# Stackduino-SMD.net
KiCad netlist of a schematic drawn in EAGLE
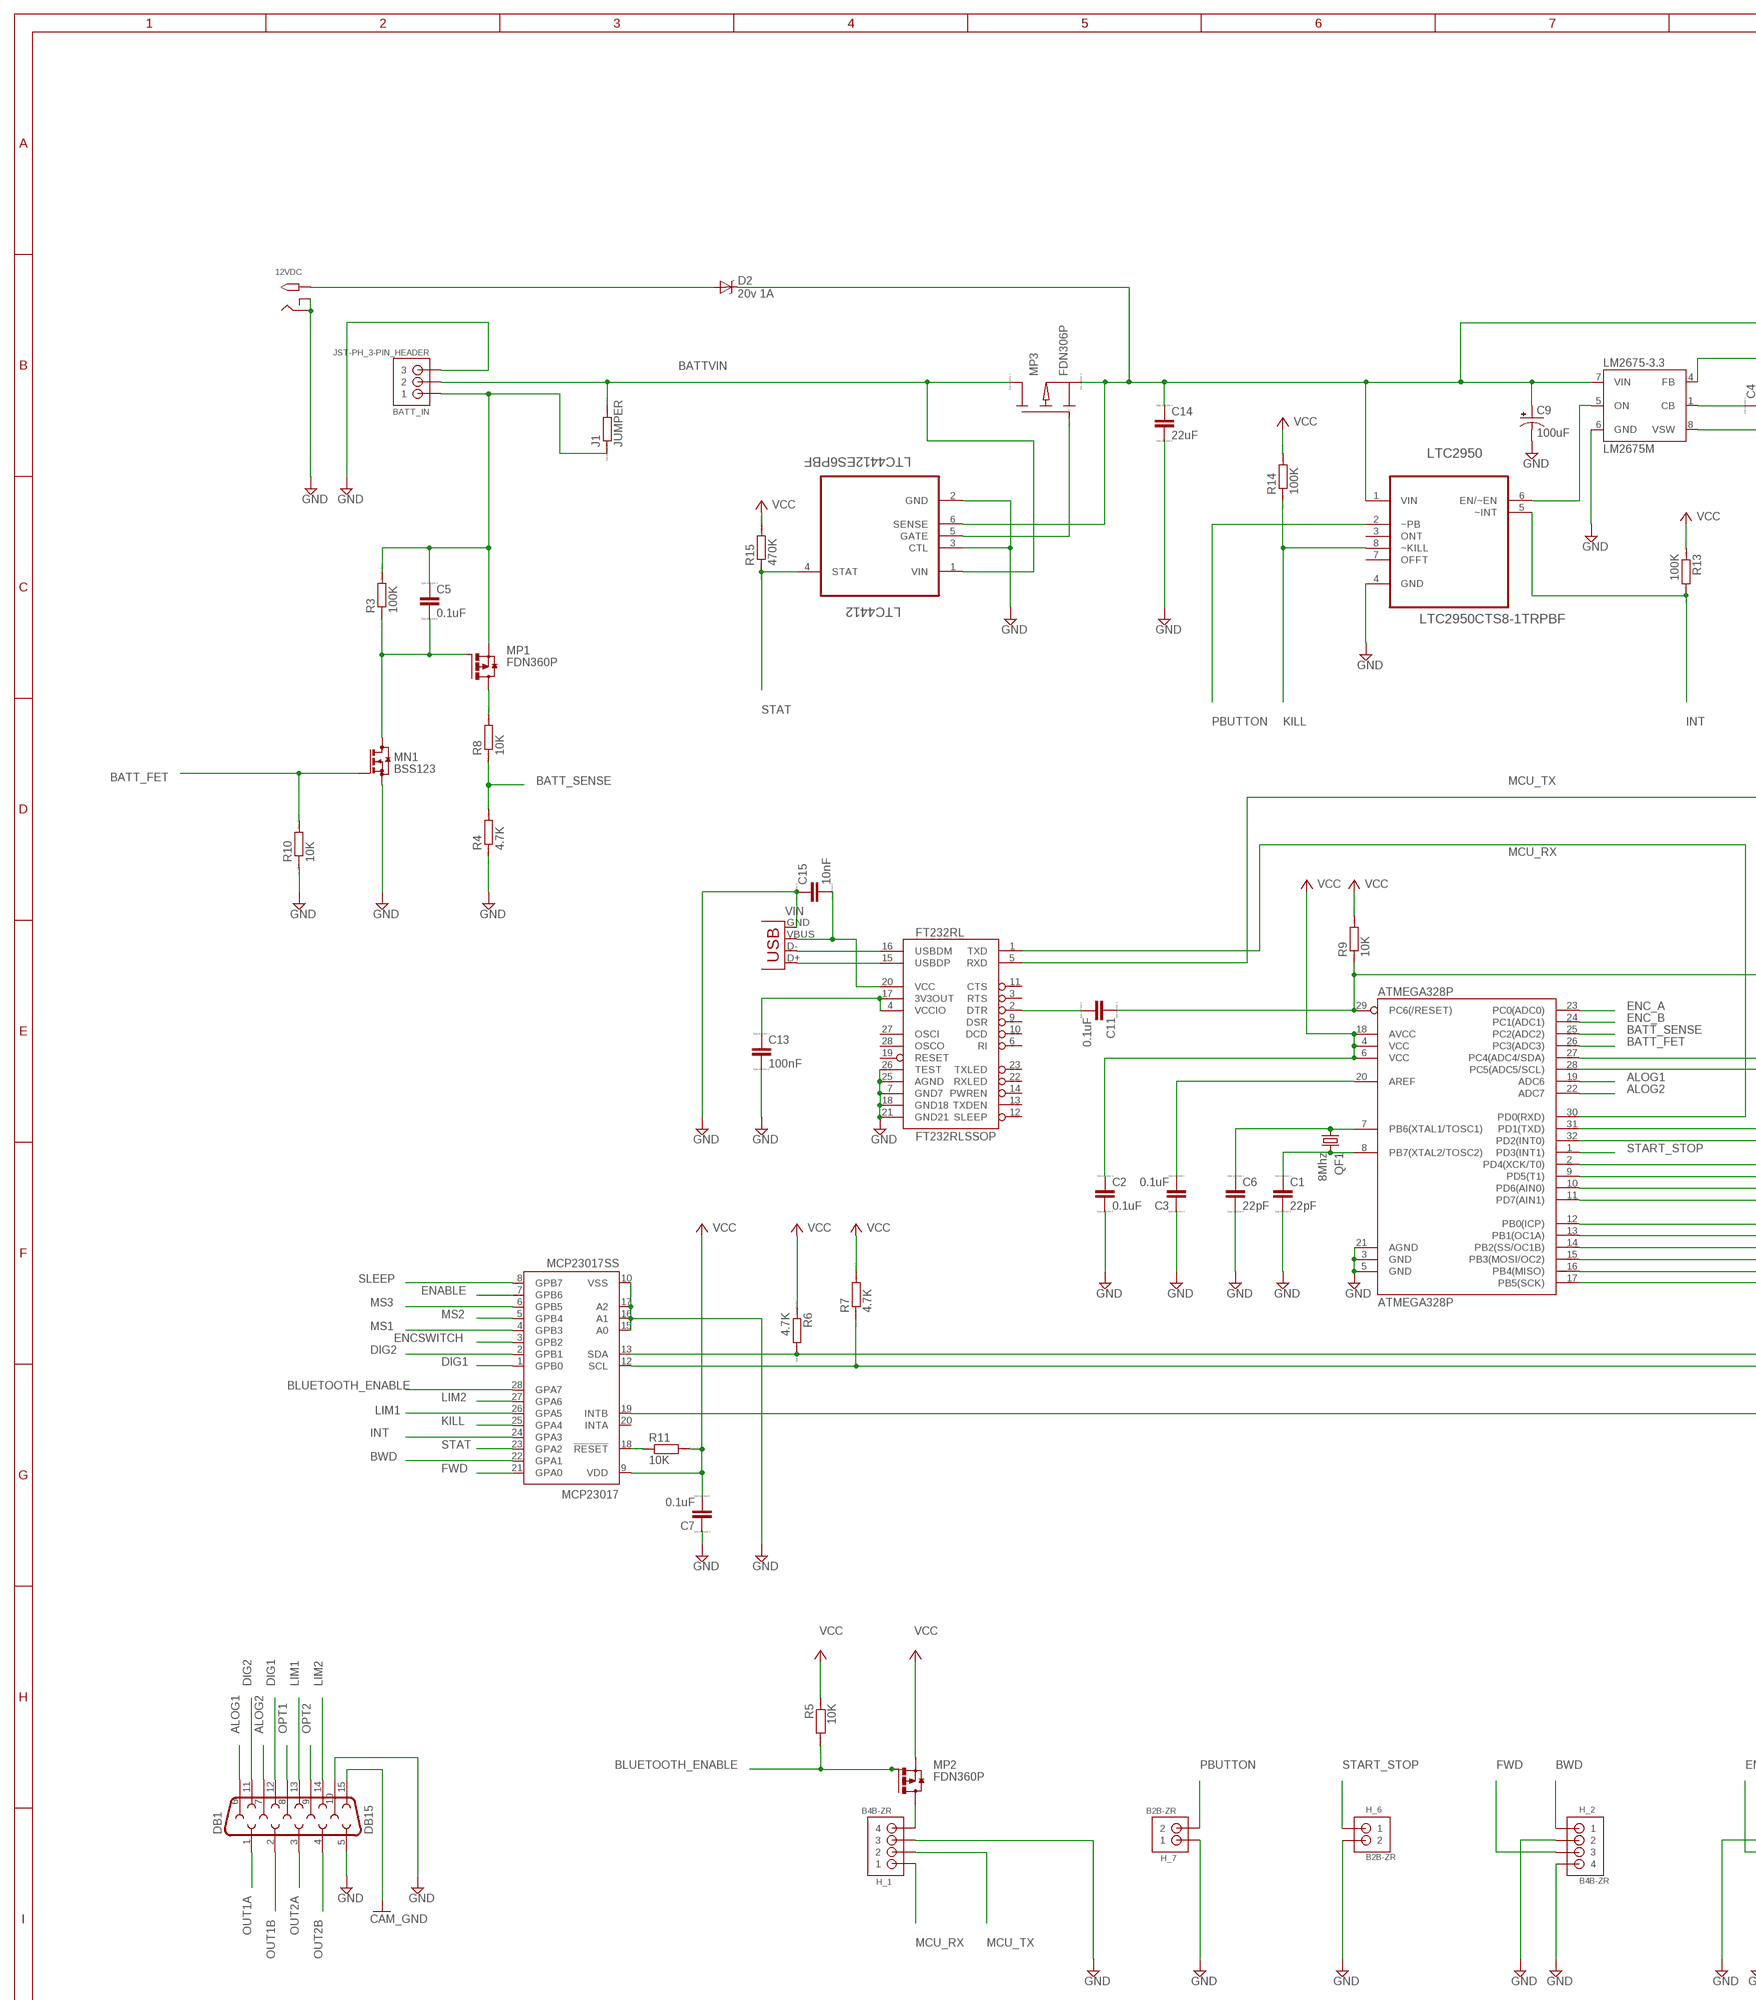
[diagram p0: schematic, sheet 1, part 1 of 2]
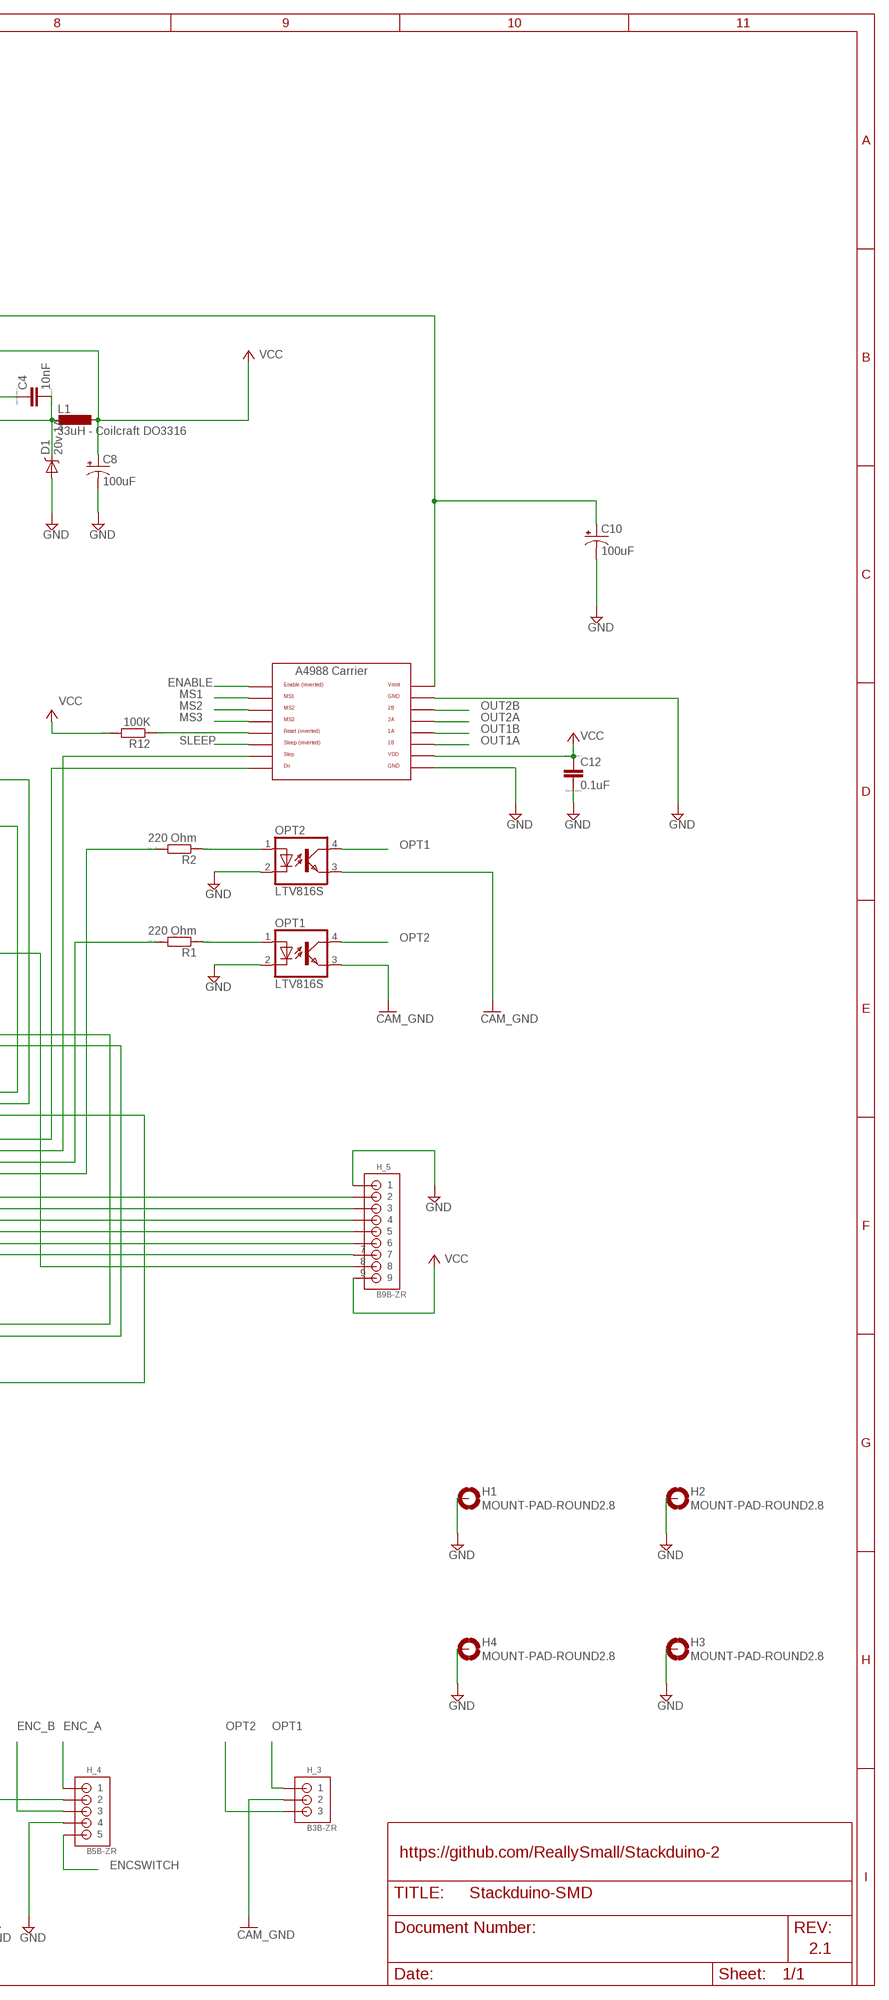
[diagram p1: schematic, sheet 1, part 2 of 2]

(export (version "E")
  (design (tool "Eeschema 10.0.6"))
  (components
    (comp (ref "12VDC")
      (value "2.1MMJACKTHM")
      (footprint "eagle-import:PJ-102A")
      (libsource (lib "eagle-import") (part "2.1MMJACKTHM"))
    )
    (comp (ref "A4988_CARRIER")
      (value "A4988BREAKOUT")
      (footprint "eagle-import:A4988BREAKOUT")
      (libsource (lib "eagle-import") (part "A4988BREAKOUT"))
    )
    (comp (ref "ATMEGA328P")
      (value "ATMEGA328P")
      (footprint "eagle-import:TQFP32-08")
      (libsource (lib "eagle-import") (part "ATMEGA328_SMT"))
    )
    (comp (ref "BATT_IN")
      (value "JST-PH_3-PIN_HEADER")
      (footprint "eagle-import:JST_B3B-PH_HEADER")
      (libsource (lib "eagle-import") (part "JST-PH_3-PIN_HEADER"))
    )
    (comp (ref "C1")
      (value "22pF")
      (footprint "eagle-import:C0805")
      (libsource (lib "eagle-import") (part "C"))
    )
    (comp (ref "C2")
      (value "0.1uF")
      (footprint "eagle-import:C0805")
      (libsource (lib "eagle-import") (part "C"))
    )
    (comp (ref "C3")
      (value "0.1uF")
      (footprint "eagle-import:C0805")
      (libsource (lib "eagle-import") (part "C"))
    )
    (comp (ref "C4")
      (value "10nF")
      (footprint "eagle-import:C0805")
      (libsource (lib "eagle-import") (part "C"))
    )
    (comp (ref "C5")
      (value "0.1uF")
      (footprint "eagle-import:C0805")
      (libsource (lib "eagle-import") (part "C"))
    )
    (comp (ref "C6")
      (value "22pF")
      (footprint "eagle-import:C0805")
      (libsource (lib "eagle-import") (part "C"))
    )
    (comp (ref "C7")
      (value "0.1uF")
      (footprint "eagle-import:C0805")
      (libsource (lib "eagle-import") (part "C"))
    )
    (comp (ref "C8")
      (value "100uF")
      (footprint "eagle-import:PANASONIC_D")
      (libsource (lib "eagle-import") (part "CAP_POLD"))
    )
    (comp (ref "C9")
      (value "100uF")
      (footprint "eagle-import:PANASONIC_D")
      (libsource (lib "eagle-import") (part "CAP_POLD"))
    )
    (comp (ref "C10")
      (value "100uF")
      (footprint "eagle-import:PANASONIC_D")
      (libsource (lib "eagle-import") (part "CAP_POLD"))
    )
    (comp (ref "C11")
      (value "0.1uF")
      (footprint "eagle-import:C0805")
      (libsource (lib "eagle-import") (part "C"))
    )
    (comp (ref "C12")
      (value "0.1uF")
      (footprint "eagle-import:C0805")
      (libsource (lib "eagle-import") (part "C"))
    )
    (comp (ref "C13")
      (value "100nF")
      (footprint "eagle-import:C0805")
      (libsource (lib "eagle-import") (part "C"))
    )
    (comp (ref "C14")
      (value "22uF")
      (footprint "eagle-import:C0805")
      (libsource (lib "eagle-import") (part "C"))
    )
    (comp (ref "C15")
      (value "10nF")
      (footprint "eagle-import:C0805")
      (libsource (lib "eagle-import") (part "C"))
    )
    (comp (ref "D1")
      (value "20v 1A")
      (footprint "eagle-import:SMA-DIODE")
      (libsource (lib "eagle-import") (part "MBRA140"))
    )
    (comp (ref "D2")
      (value "20v 1A")
      (footprint "eagle-import:SMA-DIODE")
      (libsource (lib "eagle-import") (part "MBRA140"))
    )
    (comp (ref "DB1")
      (value "DB15")
      (footprint "eagle-import:DB15")
      (libsource (lib "eagle-import") (part "DB15"))
    )
    (comp (ref "FT232RL")
      (value "FT232RLSSOP")
      (footprint "eagle-import:SSOP28DB")
      (libsource (lib "eagle-import") (part "FT232RLSSOP"))
    )
    (comp (ref "H1")
      (value "MOUNT-PAD-ROUND2.8")
      (footprint "eagle-import:2,8-PAD")
      (libsource (lib "eagle-import") (part "MOUNT-PAD-ROUND2.8"))
    )
    (comp (ref "H2")
      (value "MOUNT-PAD-ROUND2.8")
      (footprint "eagle-import:2,8-PAD")
      (libsource (lib "eagle-import") (part "MOUNT-PAD-ROUND2.8"))
    )
    (comp (ref "H3")
      (value "MOUNT-PAD-ROUND2.8")
      (footprint "eagle-import:2,8-PAD")
      (libsource (lib "eagle-import") (part "MOUNT-PAD-ROUND2.8"))
    )
    (comp (ref "H4")
      (value "MOUNT-PAD-ROUND2.8")
      (footprint "eagle-import:2,8-PAD")
      (libsource (lib "eagle-import") (part "MOUNT-PAD-ROUND2.8"))
    )
    (comp (ref "H_1")
      (value "B4B-ZR")
      (footprint "eagle-import:B4B-ZR")
      (libsource (lib "eagle-import") (part "B4B-ZR"))
    )
    (comp (ref "H_2")
      (value "B4B-ZR")
      (footprint "eagle-import:B4B-ZR")
      (libsource (lib "eagle-import") (part "B4B-ZR"))
    )
    (comp (ref "H_3")
      (value "B3B-ZR")
      (footprint "eagle-import:B3B-ZR")
      (libsource (lib "eagle-import") (part "B3B-ZR"))
    )
    (comp (ref "H_4")
      (value "B5B-ZR")
      (footprint "eagle-import:B5B-ZR")
      (libsource (lib "eagle-import") (part "B5B-ZR"))
    )
    (comp (ref "H_5")
      (value "B9B-ZR")
      (footprint "eagle-import:B9B-ZR")
      (libsource (lib "eagle-import") (part "B9B-ZR"))
    )
    (comp (ref "H_6")
      (value "B2B-ZR")
      (footprint "eagle-import:B2B-ZR")
      (libsource (lib "eagle-import") (part "B2B-ZR"))
    )
    (comp (ref "H_7")
      (value "B2B-ZR")
      (footprint "eagle-import:B2B-ZR")
      (libsource (lib "eagle-import") (part "B2B-ZR"))
    )
    (comp (ref "J1")
      (value "JUMPER")
      (footprint "eagle-import:R0805")
      (libsource (lib "eagle-import") (part "R"))
    )
    (comp (ref "L1")
      (value "33uH - Coilcraft DO3316")
      (footprint "eagle-import:DO3316P")
      (libsource (lib "eagle-import") (part "DO3316P"))
    )
    (comp (ref "LM2675-3.3")
      (value "LM2675M")
      (footprint "eagle-import:SO08")
      (libsource (lib "eagle-import") (part "LM2675M"))
    )
    (comp (ref "LTC2950")
      (value "LTC2950CTS8-1TRPBF")
      (footprint "eagle-import:SOT65P280X100-8N")
      (fields (field (name "MPN") "LTC2950CTS8-1#TRPBF"))
      (libsource (lib "eagle-import") (part "LTC2950CTS8-1TRPBF"))
    )
    (comp (ref "LTC4412")
      (value "LTC4412ES6PBF")
      (footprint "eagle-import:SOT95P280X100-6N")
      (fields (field (name "MPN") "LTC4412ES6#PBF"))
      (libsource (lib "eagle-import") (part "LTC4412ES6PBF"))
    )
    (comp (ref "MCP23017")
      (value "MCP23017SS")
      (footprint "eagle-import:SSOP28")
      (libsource (lib "eagle-import") (part "MCP23017SS"))
    )
    (comp (ref "MN1")
      (value "BSS123")
      (footprint "eagle-import:SOT23")
      (libsource (lib "eagle-import") (part "BSS123"))
    )
    (comp (ref "MP1")
      (value "FDN360P")
      (footprint "eagle-import:SUPER-SOT3")
      (libsource (lib "eagle-import") (part "FDN360P"))
    )
    (comp (ref "MP2")
      (value "FDN360P")
      (footprint "eagle-import:SUPER-SOT3")
      (libsource (lib "eagle-import") (part "FDN360P"))
    )
    (comp (ref "MP3")
      (value "FDN306P")
      (footprint "eagle-import:SOT23")
      (libsource (lib "eagle-import") (part "PMOS"))
    )
    (comp (ref "OPT1")
      (value "LTV816S")
      (footprint "eagle-import:SMD4")
      (libsource (lib "eagle-import") (part "LTV816S"))
    )
    (comp (ref "OPT2")
      (value "LTV816S")
      (footprint "eagle-import:SMD4")
      (libsource (lib "eagle-import") (part "LTV816S"))
    )
    (comp (ref "QF1")
      (value "8Mhz")
      (footprint "eagle-import:HC49U-V")
      (libsource (lib "eagle-import") (part "CRYSTALHC49U-V"))
    )
    (comp (ref "R1")
      (value "220 Ohm")
      (footprint "eagle-import:R0805")
      (libsource (lib "eagle-import") (part "R"))
    )
    (comp (ref "R2")
      (value "220 Ohm")
      (footprint "eagle-import:R0805")
      (libsource (lib "eagle-import") (part "R"))
    )
    (comp (ref "R3")
      (value "100K")
      (footprint "eagle-import:R0805")
      (libsource (lib "eagle-import") (part "R"))
    )
    (comp (ref "R4")
      (value "4.7K")
      (footprint "eagle-import:R0805")
      (libsource (lib "eagle-import") (part "R"))
    )
    (comp (ref "R5")
      (value "10K")
      (footprint "eagle-import:R0805")
      (libsource (lib "eagle-import") (part "R"))
    )
    (comp (ref "R6")
      (value "4.7K")
      (footprint "eagle-import:R0805")
      (libsource (lib "eagle-import") (part "R"))
    )
    (comp (ref "R7")
      (value "4.7K")
      (footprint "eagle-import:R0805")
      (libsource (lib "eagle-import") (part "R"))
    )
    (comp (ref "R8")
      (value "10K")
      (footprint "eagle-import:R0805")
      (libsource (lib "eagle-import") (part "R"))
    )
    (comp (ref "R9")
      (value "10K")
      (footprint "eagle-import:R0805")
      (libsource (lib "eagle-import") (part "R"))
    )
    (comp (ref "R10")
      (value "10K")
      (footprint "eagle-import:R0805")
      (libsource (lib "eagle-import") (part "R"))
    )
    (comp (ref "R11")
      (value "10K")
      (footprint "eagle-import:R0805")
      (libsource (lib "eagle-import") (part "R"))
    )
    (comp (ref "R12")
      (value "100K")
      (footprint "eagle-import:R0805")
      (libsource (lib "eagle-import") (part "R"))
    )
    (comp (ref "R13")
      (value "100K")
      (footprint "eagle-import:R0805")
      (libsource (lib "eagle-import") (part "R"))
    )
    (comp (ref "R14")
      (value "100K")
      (footprint "eagle-import:R0805")
      (libsource (lib "eagle-import") (part "R"))
    )
    (comp (ref "R15")
      (value "470K")
      (footprint "eagle-import:R0805")
      (libsource (lib "eagle-import") (part "R"))
    )
    (comp (ref "USB")
      (value "USBSMD")
      (footprint "eagle-import:USB-MINIB")
      (libsource (lib "eagle-import") (part "USBSMD"))
    )
  )
  (nets
    (net (code "1") (name "/ALOG1") (class "Default")
      (node (ref "ATMEGA328P") (pin "19") (pinfunction "ADC6_19") (pintype "bidirectional"))
      (node (ref "DB1") (pin "6") (pinfunction "6_6") (pintype "passive"))
    )
    (net (code "2") (name "/ALOG2") (class "Default")
      (node (ref "ATMEGA328P") (pin "22") (pinfunction "ADC7_22") (pintype "bidirectional"))
      (node (ref "DB1") (pin "7") (pinfunction "7_7") (pintype "passive"))
    )
    (net (code "3") (name "/BATTVIN") (class "Default")
      (node (ref "BATT_IN") (pin "P2") (pinfunction "2_P2") (pintype "bidirectional"))
      (node (ref "J1") (pin "2") (pinfunction "2_2") (pintype "passive"))
      (node (ref "LTC4412") (pin "1") (pinfunction "VIN_1") (pintype "power_in"))
      (node (ref "MP3") (pin "3") (pinfunction "D_3") (pintype "passive"))
    )
    (net (code "4") (name "/BATT_FET") (class "Default")
      (node (ref "ATMEGA328P") (pin "26") (pinfunction "PC3(ADC3)_26") (pintype "bidirectional"))
      (node (ref "MN1") (pin "1") (pinfunction "G_1") (pintype "passive"))
      (node (ref "R10") (pin "2") (pinfunction "2_2") (pintype "passive"))
    )
    (net (code "5") (name "/BATT_SENSE") (class "Default")
      (node (ref "ATMEGA328P") (pin "25") (pinfunction "PC2(ADC2)_25") (pintype "bidirectional"))
      (node (ref "R4") (pin "2") (pinfunction "2_2") (pintype "passive"))
      (node (ref "R8") (pin "1") (pinfunction "1_1") (pintype "passive"))
    )
    (net (code "6") (name "/BLUETOOTH_ENABLE") (class "Default")
      (node (ref "MCP23017") (pin "28") (pinfunction "GPA7_28") (pintype "bidirectional"))
      (node (ref "MP2") (pin "1") (pinfunction "G_1") (pintype "passive"))
      (node (ref "R5") (pin "2") (pinfunction "2_2") (pintype "passive"))
    )
    (net (code "7") (name "/BWD") (class "Default")
      (node (ref "H_2") (pin "1") (pinfunction "1_1") (pintype "bidirectional"))
      (node (ref "MCP23017") (pin "22") (pinfunction "GPA1_22") (pintype "bidirectional"))
    )
    (net (code "8") (name "/DIG1") (class "Default")
      (node (ref "DB1") (pin "12") (pinfunction "12_12") (pintype "passive"))
      (node (ref "MCP23017") (pin "1") (pinfunction "GPB0_1") (pintype "bidirectional"))
    )
    (net (code "9") (name "/DIG2") (class "Default")
      (node (ref "DB1") (pin "11") (pinfunction "11_11") (pintype "passive"))
      (node (ref "MCP23017") (pin "2") (pinfunction "GPB1_2") (pintype "bidirectional"))
    )
    (net (code "10") (name "/ENABLE") (class "Default")
      (node (ref "A4988_CARRIER") (pin "EN") (pinfunction "EN_EN") (pintype "input"))
      (node (ref "MCP23017") (pin "7") (pinfunction "GPB6_7") (pintype "bidirectional"))
    )
    (net (code "11") (name "/ENCSWITCH") (class "Default")
      (node (ref "H_4") (pin "5") (pinfunction "5_5") (pintype "bidirectional"))
      (node (ref "MCP23017") (pin "3") (pinfunction "GPB2_3") (pintype "bidirectional"))
    )
    (net (code "12") (name "/ENC_A") (class "Default")
      (node (ref "ATMEGA328P") (pin "23") (pinfunction "PC0(ADC0)_23") (pintype "bidirectional"))
      (node (ref "H_4") (pin "1") (pinfunction "1_1") (pintype "bidirectional"))
    )
    (net (code "13") (name "/ENC_B") (class "Default")
      (node (ref "ATMEGA328P") (pin "24") (pinfunction "PC1(ADC1)_24") (pintype "bidirectional"))
      (node (ref "H_4") (pin "3") (pinfunction "3_3") (pintype "bidirectional"))
    )
    (net (code "14") (name "/FWD") (class "Default")
      (node (ref "H_2") (pin "3") (pinfunction "3_3") (pintype "bidirectional"))
      (node (ref "MCP23017") (pin "21") (pinfunction "GPA0_21") (pintype "bidirectional"))
    )
    (net (code "15") (name "/INT") (class "Default")
      (node (ref "LTC2950") (pin "5") (pinfunction "~{INT}_5") (pintype "output"))
      (node (ref "MCP23017") (pin "24") (pinfunction "GPA3_24") (pintype "bidirectional"))
      (node (ref "R13") (pin "2") (pinfunction "2_2") (pintype "passive"))
    )
    (net (code "16") (name "/KILL") (class "Default")
      (node (ref "LTC2950") (pin "8") (pinfunction "~{KILL}_8") (pintype "input"))
      (node (ref "MCP23017") (pin "25") (pinfunction "GPA4_25") (pintype "bidirectional"))
      (node (ref "R14") (pin "1") (pinfunction "1_1") (pintype "passive"))
    )
    (net (code "17") (name "/LIM1") (class "Default")
      (node (ref "DB1") (pin "13") (pinfunction "13_13") (pintype "passive"))
      (node (ref "MCP23017") (pin "26") (pinfunction "GPA5_26") (pintype "bidirectional"))
    )
    (net (code "18") (name "/LIM2") (class "Default")
      (node (ref "DB1") (pin "14") (pinfunction "14_14") (pintype "passive"))
      (node (ref "MCP23017") (pin "27") (pinfunction "GPA6_27") (pintype "bidirectional"))
    )
    (net (code "19") (name "/MCU_RX") (class "Default")
      (node (ref "ATMEGA328P") (pin "30") (pinfunction "PD0(RXD)_30") (pintype "bidirectional"))
      (node (ref "FT232RL") (pin "1") (pinfunction "TXD_1") (pintype "output"))
      (node (ref "H_1") (pin "1") (pinfunction "1_1") (pintype "bidirectional"))
    )
    (net (code "20") (name "/MCU_TX") (class "Default")
      (node (ref "ATMEGA328P") (pin "31") (pinfunction "PD1(TXD)_31") (pintype "bidirectional"))
      (node (ref "FT232RL") (pin "5") (pinfunction "RXD_5") (pintype "input"))
      (node (ref "H_1") (pin "2") (pinfunction "2_2") (pintype "bidirectional"))
    )
    (net (code "21") (name "/MS1") (class "Default")
      (node (ref "A4988_CARRIER") (pin "MS1") (pinfunction "MS1_MS1") (pintype "input"))
      (node (ref "MCP23017") (pin "4") (pinfunction "GPB3_4") (pintype "bidirectional"))
    )
    (net (code "22") (name "/MS2") (class "Default")
      (node (ref "A4988_CARRIER") (pin "MS2") (pinfunction "MS2_MS2") (pintype "input"))
      (node (ref "MCP23017") (pin "5") (pinfunction "GPB4_5") (pintype "bidirectional"))
    )
    (net (code "23") (name "/MS3") (class "Default")
      (node (ref "A4988_CARRIER") (pin "MS3") (pinfunction "MS3_MS3") (pintype "input"))
      (node (ref "MCP23017") (pin "6") (pinfunction "GPB5_6") (pintype "bidirectional"))
    )
    (net (code "24") (name "/OPT1") (class "Default")
      (node (ref "DB1") (pin "8") (pinfunction "8_8") (pintype "passive"))
      (node (ref "H_3") (pin "1") (pinfunction "1_1") (pintype "bidirectional"))
      (node (ref "OPT2") (pin "4") (pinfunction "COL_4") (pintype "passive"))
    )
    (net (code "25") (name "/OPT2") (class "Default")
      (node (ref "DB1") (pin "9") (pinfunction "9_9") (pintype "passive"))
      (node (ref "H_3") (pin "3") (pinfunction "3_3") (pintype "bidirectional"))
      (node (ref "OPT1") (pin "4") (pinfunction "COL_4") (pintype "passive"))
    )
    (net (code "26") (name "/OUT1A") (class "Default")
      (node (ref "A4988_CARRIER") (pin "1B") (pinfunction "1B_1B") (pintype "output"))
      (node (ref "DB1") (pin "1") (pinfunction "1_1") (pintype "passive"))
    )
    (net (code "27") (name "/OUT1B") (class "Default")
      (node (ref "A4988_CARRIER") (pin "1A") (pinfunction "1A_1A") (pintype "output"))
      (node (ref "DB1") (pin "2") (pinfunction "2_2") (pintype "passive"))
    )
    (net (code "28") (name "/OUT2A") (class "Default")
      (node (ref "A4988_CARRIER") (pin "2A") (pinfunction "2A_2A") (pintype "output"))
      (node (ref "DB1") (pin "3") (pinfunction "3_3") (pintype "passive"))
    )
    (net (code "29") (name "/OUT2B") (class "Default")
      (node (ref "A4988_CARRIER") (pin "2B") (pinfunction "2B_2B") (pintype "output"))
      (node (ref "DB1") (pin "4") (pinfunction "4_4") (pintype "passive"))
    )
    (net (code "30") (name "/PBUTTON") (class "Default")
      (node (ref "H_7") (pin "2") (pinfunction "2_2") (pintype "bidirectional"))
      (node (ref "LTC2950") (pin "2") (pinfunction "~{PB}_2") (pintype "input"))
    )
    (net (code "31") (name "/SLEEP") (class "Default")
      (node (ref "A4988_CARRIER") (pin "SLP") (pinfunction "SLEEP_SLP") (pintype "input"))
      (node (ref "MCP23017") (pin "8") (pinfunction "GPB7_8") (pintype "bidirectional"))
    )
    (net (code "32") (name "/START_STOP") (class "Default")
      (node (ref "ATMEGA328P") (pin "1") (pinfunction "PD3(INT1)_1") (pintype "bidirectional"))
      (node (ref "H_6") (pin "1") (pinfunction "1_1") (pintype "bidirectional"))
    )
    (net (code "33") (name "/STAT") (class "Default")
      (node (ref "LTC4412") (pin "4") (pinfunction "STAT_4") (pintype "output"))
      (node (ref "MCP23017") (pin "23") (pinfunction "GPA2_23") (pintype "bidirectional"))
      (node (ref "R15") (pin "1") (pinfunction "1_1") (pintype "passive"))
    )
    (net (code "34") (name "/VIN") (class "Default")
      (node (ref "12VDC") (pin "TIP") (pinfunction "TIP_TIP") (pintype "bidirectional"))
      (node (ref "D2") (pin "A") (pinfunction "A_A") (pintype "passive"))
    )
    (net (code "35") (name "CAM_GND") (class "Default")
      (node (ref "DB1") (pin "15") (pinfunction "15_15") (pintype "passive"))
      (node (ref "H_3") (pin "2") (pinfunction "2_2") (pintype "bidirectional"))
      (node (ref "OPT1") (pin "3") (pinfunction "EMIT_3") (pintype "passive"))
      (node (ref "OPT2") (pin "3") (pinfunction "EMIT_3") (pintype "passive"))
    )
    (net (code "36") (name "GND") (class "Default")
      (node (ref "12VDC") (pin "RING") (pinfunction "RING_RING") (pintype "bidirectional"))
      (node (ref "12VDC") (pin "RING_SW") (pinfunction "RING_SW_RING_SW") (pintype "bidirectional"))
      (node (ref "A4988_CARRIER") (pin "GND") (pinfunction "GND_GND") (pintype "power_in"))
      (node (ref "A4988_CARRIER") (pin "GND@0") (pinfunction "GND_GND@0") (pintype "power_in"))
      (node (ref "ATMEGA328P") (pin "21") (pinfunction "AGND_21") (pintype "bidirectional"))
      (node (ref "ATMEGA328P") (pin "3") (pinfunction "GND_3") (pintype "bidirectional"))
      (node (ref "ATMEGA328P") (pin "5") (pinfunction "GND_5") (pintype "bidirectional"))
      (node (ref "BATT_IN") (pin "P3") (pinfunction "3_P3") (pintype "bidirectional"))
      (node (ref "C1") (pin "2") (pinfunction "2_2") (pintype "passive"))
      (node (ref "C10") (pin "-") (pinfunction "-_-") (pintype "passive"))
      (node (ref "C12") (pin "2") (pinfunction "2_2") (pintype "passive"))
      (node (ref "C13") (pin "2") (pinfunction "2_2") (pintype "passive"))
      (node (ref "C14") (pin "2") (pinfunction "2_2") (pintype "passive"))
      (node (ref "C15") (pin "1") (pinfunction "1_1") (pintype "passive"))
      (node (ref "C2") (pin "2") (pinfunction "2_2") (pintype "passive"))
      (node (ref "C3") (pin "1") (pinfunction "1_1") (pintype "passive"))
      (node (ref "C6") (pin "2") (pinfunction "2_2") (pintype "passive"))
      (node (ref "C7") (pin "1") (pinfunction "1_1") (pintype "passive"))
      (node (ref "C8") (pin "-") (pinfunction "-_-") (pintype "passive"))
      (node (ref "C9") (pin "-") (pinfunction "-_-") (pintype "passive"))
      (node (ref "D1") (pin "A") (pinfunction "A_A") (pintype "passive"))
      (node (ref "DB1") (pin "10") (pinfunction "10_10") (pintype "passive"))
      (node (ref "DB1") (pin "5") (pinfunction "5_5") (pintype "passive"))
      (node (ref "FT232RL") (pin "18") (pinfunction "GND18_18") (pintype "power_in"))
      (node (ref "FT232RL") (pin "21") (pinfunction "GND21_21") (pintype "power_in"))
      (node (ref "FT232RL") (pin "25") (pinfunction "AGND_25") (pintype "power_in"))
      (node (ref "FT232RL") (pin "26") (pinfunction "TEST_26") (pintype "input"))
      (node (ref "FT232RL") (pin "7") (pinfunction "GND7_7") (pintype "power_in"))
      (node (ref "H1") (pin "B2,8") (pinfunction "MOUNT_B2,8") (pintype "passive"))
      (node (ref "H2") (pin "B2,8") (pinfunction "MOUNT_B2,8") (pintype "passive"))
      (node (ref "H3") (pin "B2,8") (pinfunction "MOUNT_B2,8") (pintype "passive"))
      (node (ref "H4") (pin "B2,8") (pinfunction "MOUNT_B2,8") (pintype "passive"))
      (node (ref "H_1") (pin "3") (pinfunction "3_3") (pintype "bidirectional"))
      (node (ref "H_2") (pin "2") (pinfunction "2_2") (pintype "bidirectional"))
      (node (ref "H_2") (pin "4") (pinfunction "4_4") (pintype "bidirectional"))
      (node (ref "H_4") (pin "2") (pinfunction "2_2") (pintype "bidirectional"))
      (node (ref "H_4") (pin "4") (pinfunction "4_4") (pintype "bidirectional"))
      (node (ref "H_5") (pin "1") (pinfunction "1_1") (pintype "bidirectional"))
      (node (ref "H_6") (pin "2") (pinfunction "2_2") (pintype "bidirectional"))
      (node (ref "H_7") (pin "1") (pinfunction "1_1") (pintype "bidirectional"))
      (node (ref "LM2675-3.3") (pin "6") (pinfunction "GND_6") (pintype "power_in"))
      (node (ref "LTC2950") (pin "4") (pinfunction "GND_4") (pintype "passive"))
      (node (ref "LTC4412") (pin "2") (pinfunction "GND_2") (pintype "passive"))
      (node (ref "LTC4412") (pin "3") (pinfunction "CTL_3") (pintype "input"))
      (node (ref "MCP23017") (pin "10") (pinfunction "VSS_10") (pintype "power_in"))
      (node (ref "MCP23017") (pin "15") (pinfunction "A0_15") (pintype "input"))
      (node (ref "MCP23017") (pin "16") (pinfunction "A1_16") (pintype "input"))
      (node (ref "MCP23017") (pin "17") (pinfunction "A2_17") (pintype "input"))
      (node (ref "MN1") (pin "2") (pinfunction "S_2") (pintype "passive"))
      (node (ref "OPT1") (pin "2") (pinfunction "C_2") (pintype "passive"))
      (node (ref "OPT2") (pin "2") (pinfunction "C_2") (pintype "passive"))
      (node (ref "R10") (pin "1") (pinfunction "1_1") (pintype "passive"))
      (node (ref "R4") (pin "1") (pinfunction "1_1") (pintype "passive"))
      (node (ref "USB") (pin "GND") (pinfunction "GND_GND") (pintype "bidirectional"))
    )
    (net (code "37") (name "Net-(A4988_CARRIER-PadRST)") (class "Default")
      (node (ref "A4988_CARRIER") (pin "RST") (pinfunction "RST_RST") (pintype "input"))
      (node (ref "R12") (pin "1") (pinfunction "1_1") (pintype "passive"))
    )
    (net (code "38") (name "Net-(ATMEGA328P-AREF)") (class "Default")
      (node (ref "ATMEGA328P") (pin "20") (pinfunction "AREF_20") (pintype "bidirectional"))
      (node (ref "C3") (pin "2") (pinfunction "2_2") (pintype "passive"))
    )
    (net (code "39") (name "Net-(ATMEGA328P-PB0(ICP))") (class "Default")
      (node (ref "ATMEGA328P") (pin "12") (pinfunction "PB0(ICP)_12") (pintype "bidirectional"))
      (node (ref "H_5") (pin "2") (pinfunction "2_2") (pintype "bidirectional"))
    )
    (net (code "40") (name "Net-(ATMEGA328P-PB1(OC1A))") (class "Default")
      (node (ref "ATMEGA328P") (pin "13") (pinfunction "PB1(OC1A)_13") (pintype "bidirectional"))
      (node (ref "H_5") (pin "3") (pinfunction "3_3") (pintype "bidirectional"))
    )
    (net (code "41") (name "Net-(ATMEGA328P-PB2(SS{slash}OC1B))") (class "Default")
      (node (ref "ATMEGA328P") (pin "14") (pinfunction "PB2(SS/OC1B)_14") (pintype "bidirectional"))
      (node (ref "H_5") (pin "4") (pinfunction "4_4") (pintype "bidirectional"))
    )
    (net (code "42") (name "Net-(ATMEGA328P-PB3(MOSI{slash}OC2))") (class "Default")
      (node (ref "ATMEGA328P") (pin "15") (pinfunction "PB3(MOSI/OC2)_15") (pintype "bidirectional"))
      (node (ref "H_5") (pin "5") (pinfunction "5_5") (pintype "bidirectional"))
    )
    (net (code "43") (name "Net-(ATMEGA328P-PB4(MISO))") (class "Default")
      (node (ref "ATMEGA328P") (pin "16") (pinfunction "PB4(MISO)_16") (pintype "bidirectional"))
      (node (ref "H_5") (pin "6") (pinfunction "6_6") (pintype "bidirectional"))
    )
    (net (code "44") (name "Net-(ATMEGA328P-PB5(SCK))") (class "Default")
      (node (ref "ATMEGA328P") (pin "17") (pinfunction "PB5(SCK)_17") (pintype "bidirectional"))
      (node (ref "H_5") (pin "7") (pinfunction "7_7") (pintype "bidirectional"))
    )
    (net (code "45") (name "Net-(ATMEGA328P-PB6(XTAL1{slash}TOSC1))") (class "Default")
      (node (ref "ATMEGA328P") (pin "7") (pinfunction "PB6(XTAL1/TOSC1)_7") (pintype "bidirectional"))
      (node (ref "C6") (pin "1") (pinfunction "1_1") (pintype "passive"))
      (node (ref "QF1") (pin "1") (pinfunction "1_1") (pintype "passive"))
    )
    (net (code "46") (name "Net-(ATMEGA328P-PB7(XTAL2{slash}TOSC2))") (class "Default")
      (node (ref "ATMEGA328P") (pin "8") (pinfunction "PB7(XTAL2/TOSC2)_8") (pintype "bidirectional"))
      (node (ref "C1") (pin "1") (pinfunction "1_1") (pintype "passive"))
      (node (ref "QF1") (pin "2") (pinfunction "2_2") (pintype "passive"))
    )
    (net (code "47") (name "Net-(ATMEGA328P-PC4(ADC4{slash}SDA))") (class "Default")
      (node (ref "ATMEGA328P") (pin "27") (pinfunction "PC4(ADC4/SDA)_27") (pintype "bidirectional"))
      (node (ref "MCP23017") (pin "13") (pinfunction "SDA_13") (pintype "bidirectional"))
      (node (ref "R6") (pin "2") (pinfunction "2_2") (pintype "passive"))
    )
    (net (code "48") (name "Net-(ATMEGA328P-PC5(ADC5{slash}SCL))") (class "Default")
      (node (ref "ATMEGA328P") (pin "28") (pinfunction "PC5(ADC5/SCL)_28") (pintype "bidirectional"))
      (node (ref "MCP23017") (pin "12") (pinfunction "SCL_12") (pintype "input"))
      (node (ref "R7") (pin "1") (pinfunction "1_1") (pintype "passive"))
    )
    (net (code "49") (name "Net-(ATMEGA328P-PC6({slash}RESET))") (class "Default")
      (node (ref "ATMEGA328P") (pin "29") (pinfunction "PC6(/RESET)_29") (pintype "bidirectional"))
      (node (ref "C11") (pin "1") (pinfunction "1_1") (pintype "passive"))
      (node (ref "H_5") (pin "8") (pinfunction "8_8") (pintype "bidirectional"))
      (node (ref "R9") (pin "1") (pinfunction "1_1") (pintype "passive"))
    )
    (net (code "50") (name "Net-(ATMEGA328P-PD2(INT0))") (class "Default")
      (node (ref "ATMEGA328P") (pin "32") (pinfunction "PD2(INT0)_32") (pintype "bidirectional"))
      (node (ref "MCP23017") (pin "19") (pinfunction "INTB_19") (pintype "output"))
    )
    (net (code "51") (name "Net-(ATMEGA328P-PD4(XCK{slash}T0))") (class "Default")
      (node (ref "A4988_CARRIER") (pin "DIR") (pinfunction "DIR_DIR") (pintype "input"))
      (node (ref "ATMEGA328P") (pin "2") (pinfunction "PD4(XCK/T0)_2") (pintype "bidirectional"))
    )
    (net (code "52") (name "Net-(ATMEGA328P-PD5(T1))") (class "Default")
      (node (ref "A4988_CARRIER") (pin "STEP") (pinfunction "STEP_STEP") (pintype "input"))
      (node (ref "ATMEGA328P") (pin "9") (pinfunction "PD5(T1)_9") (pintype "bidirectional"))
    )
    (net (code "53") (name "Net-(ATMEGA328P-PD6(AIN0))") (class "Default")
      (node (ref "ATMEGA328P") (pin "10") (pinfunction "PD6(AIN0)_10") (pintype "bidirectional"))
      (node (ref "R1") (pin "2") (pinfunction "2_2") (pintype "passive"))
    )
    (net (code "54") (name "Net-(ATMEGA328P-PD7(AIN1))") (class "Default")
      (node (ref "ATMEGA328P") (pin "11") (pinfunction "PD7(AIN1)_11") (pintype "bidirectional"))
      (node (ref "R2") (pin "2") (pinfunction "2_2") (pintype "passive"))
    )
    (net (code "55") (name "Net-(BATT_IN-1)") (class "Default")
      (node (ref "BATT_IN") (pin "P1") (pinfunction "1_P1") (pintype "bidirectional"))
      (node (ref "C5") (pin "1") (pinfunction "1_1") (pintype "passive"))
      (node (ref "J1") (pin "1") (pinfunction "1_1") (pintype "passive"))
      (node (ref "MP1") (pin "2") (pinfunction "S_2") (pintype "passive"))
      (node (ref "R3") (pin "2") (pinfunction "2_2") (pintype "passive"))
    )
    (net (code "56") (name "Net-(FT232RL-3V3OUT)") (class "Default")
      (node (ref "C13") (pin "1") (pinfunction "1_1") (pintype "passive"))
      (node (ref "FT232RL") (pin "17") (pinfunction "3V3OUT_17") (pintype "output"))
      (node (ref "FT232RL") (pin "4") (pinfunction "VCCIO_4") (pintype "power_in"))
    )
    (net (code "57") (name "Net-(FT232RL-DTR)") (class "Default")
      (node (ref "C11") (pin "2") (pinfunction "2_2") (pintype "passive"))
      (node (ref "FT232RL") (pin "2") (pinfunction "DTR_2") (pintype "output"))
    )
    (net (code "58") (name "Net-(FT232RL-USBDM)") (class "Default")
      (node (ref "FT232RL") (pin "16") (pinfunction "USBDM_16") (pintype "bidirectional"))
      (node (ref "USB") (pin "D-") (pinfunction "D-_D-") (pintype "bidirectional"))
    )
    (net (code "59") (name "Net-(FT232RL-USBDP)") (class "Default")
      (node (ref "FT232RL") (pin "15") (pinfunction "USBDP_15") (pintype "bidirectional"))
      (node (ref "USB") (pin "D+") (pinfunction "D+_D+") (pintype "bidirectional"))
    )
    (net (code "60") (name "Net-(FT232RL-VCC)") (class "Default")
      (node (ref "C15") (pin "2") (pinfunction "2_2") (pintype "passive"))
      (node (ref "FT232RL") (pin "20") (pinfunction "VCC_20") (pintype "power_in"))
      (node (ref "USB") (pin "VBUS") (pinfunction "VBUS_VBUS") (pintype "bidirectional"))
    )
    (net (code "61") (name "Net-(LM2675-3.3-CB)") (class "Default")
      (node (ref "C4") (pin "1") (pinfunction "1_1") (pintype "passive"))
      (node (ref "LM2675-3.3") (pin "1") (pinfunction "CB_1") (pintype "input"))
    )
    (net (code "62") (name "Net-(LM2675-3.3-ON)") (class "Default")
      (node (ref "LM2675-3.3") (pin "5") (pinfunction "ON_5") (pintype "passive"))
      (node (ref "LTC2950") (pin "6") (pinfunction "EN/~{EN}_6") (pintype "output"))
    )
    (net (code "63") (name "Net-(LM2675-3.3-VIN)") (class "Default")
      (node (ref "A4988_CARRIER") (pin "VMOT") (pinfunction "VMOT_VMOT") (pintype "power_in"))
      (node (ref "C10") (pin "+") (pinfunction "+_+") (pintype "passive"))
      (node (ref "C14") (pin "1") (pinfunction "1_1") (pintype "passive"))
      (node (ref "C9") (pin "+") (pinfunction "+_+") (pintype "passive"))
      (node (ref "D2") (pin "C") (pinfunction "C_C") (pintype "passive"))
      (node (ref "LM2675-3.3") (pin "7") (pinfunction "VIN_7") (pintype "power_in"))
      (node (ref "LTC2950") (pin "1") (pinfunction "VIN_1") (pintype "power_in"))
      (node (ref "LTC4412") (pin "6") (pinfunction "SENSE_6") (pintype "input"))
      (node (ref "MP3") (pin "2") (pinfunction "S_2") (pintype "passive"))
    )
    (net (code "64") (name "Net-(LM2675-3.3-VSW)") (class "Default")
      (node (ref "C4") (pin "2") (pinfunction "2_2") (pintype "passive"))
      (node (ref "D1") (pin "C") (pinfunction "C_C") (pintype "passive"))
      (node (ref "L1") (pin "1") (pinfunction "1_1") (pintype "passive"))
      (node (ref "LM2675-3.3") (pin "8") (pinfunction "VSW_8") (pintype "output"))
    )
    (net (code "65") (name "Net-(LTC4412-GATE)") (class "Default")
      (node (ref "LTC4412") (pin "5") (pinfunction "GATE_5") (pintype "input"))
      (node (ref "MP3") (pin "1") (pinfunction "G_1") (pintype "passive"))
    )
    (net (code "66") (name "Net-(MCP23017-~{RESET})") (class "Default")
      (node (ref "MCP23017") (pin "18") (pinfunction "~{RESET}_18") (pintype "input"))
      (node (ref "R11") (pin "1") (pinfunction "1_1") (pintype "passive"))
    )
    (net (code "67") (name "Net-(MN1-D)") (class "Default")
      (node (ref "C5") (pin "2") (pinfunction "2_2") (pintype "passive"))
      (node (ref "MN1") (pin "3") (pinfunction "D_3") (pintype "passive"))
      (node (ref "MP1") (pin "1") (pinfunction "G_1") (pintype "passive"))
      (node (ref "R3") (pin "1") (pinfunction "1_1") (pintype "passive"))
    )
    (net (code "68") (name "Net-(MP1-D)") (class "Default")
      (node (ref "MP1") (pin "3") (pinfunction "D_3") (pintype "passive"))
      (node (ref "R8") (pin "2") (pinfunction "2_2") (pintype "passive"))
    )
    (net (code "69") (name "Net-(MP2-D)") (class "Default")
      (node (ref "H_1") (pin "4") (pinfunction "4_4") (pintype "bidirectional"))
      (node (ref "MP2") (pin "3") (pinfunction "D_3") (pintype "passive"))
    )
    (net (code "70") (name "Net-(OPT1-A)") (class "Default")
      (node (ref "OPT1") (pin "1") (pinfunction "A_1") (pintype "passive"))
      (node (ref "R1") (pin "1") (pinfunction "1_1") (pintype "passive"))
    )
    (net (code "71") (name "Net-(OPT2-A)") (class "Default")
      (node (ref "OPT2") (pin "1") (pinfunction "A_1") (pintype "passive"))
      (node (ref "R2") (pin "1") (pinfunction "1_1") (pintype "passive"))
    )
    (net (code "72") (name "VCC") (class "Default")
      (node (ref "A4988_CARRIER") (pin "VDD") (pinfunction "VDD_VDD") (pintype "power_in"))
      (node (ref "ATMEGA328P") (pin "18") (pinfunction "AVCC_18") (pintype "bidirectional"))
      (node (ref "ATMEGA328P") (pin "4") (pinfunction "VCC_4") (pintype "bidirectional"))
      (node (ref "ATMEGA328P") (pin "6") (pinfunction "VCC_6") (pintype "bidirectional"))
      (node (ref "C12") (pin "1") (pinfunction "1_1") (pintype "passive"))
      (node (ref "C2") (pin "1") (pinfunction "1_1") (pintype "passive"))
      (node (ref "C7") (pin "2") (pinfunction "2_2") (pintype "passive"))
      (node (ref "C8") (pin "+") (pinfunction "+_+") (pintype "passive"))
      (node (ref "H_5") (pin "9") (pinfunction "9_9") (pintype "bidirectional"))
      (node (ref "L1") (pin "2") (pinfunction "2_2") (pintype "passive"))
      (node (ref "LM2675-3.3") (pin "4") (pinfunction "FB_4") (pintype "input"))
      (node (ref "MCP23017") (pin "9") (pinfunction "VDD_9") (pintype "power_in"))
      (node (ref "MP2") (pin "2") (pinfunction "S_2") (pintype "passive"))
      (node (ref "R11") (pin "2") (pinfunction "2_2") (pintype "passive"))
      (node (ref "R12") (pin "2") (pinfunction "2_2") (pintype "passive"))
      (node (ref "R13") (pin "1") (pinfunction "1_1") (pintype "passive"))
      (node (ref "R14") (pin "2") (pinfunction "2_2") (pintype "passive"))
      (node (ref "R15") (pin "2") (pinfunction "2_2") (pintype "passive"))
      (node (ref "R5") (pin "1") (pinfunction "1_1") (pintype "passive"))
      (node (ref "R6") (pin "1") (pinfunction "1_1") (pintype "passive"))
      (node (ref "R7") (pin "2") (pinfunction "2_2") (pintype "passive"))
      (node (ref "R9") (pin "2") (pinfunction "2_2") (pintype "passive"))
    )
    (net (code "73") (name "unconnected-(FT232RL-CTS-Pad11)") (class "Default")
      (node (ref "FT232RL") (pin "11") (pinfunction "CTS_11") (pintype "input"))
    )
    (net (code "74") (name "unconnected-(FT232RL-DCD-Pad10)") (class "Default")
      (node (ref "FT232RL") (pin "10") (pinfunction "DCD_10") (pintype "input"))
    )
    (net (code "75") (name "unconnected-(FT232RL-DSR-Pad9)") (class "Default")
      (node (ref "FT232RL") (pin "9") (pinfunction "DSR_9") (pintype "input"))
    )
    (net (code "76") (name "unconnected-(FT232RL-OSCI-Pad27)") (class "Default")
      (node (ref "FT232RL") (pin "27") (pinfunction "OSCI_27") (pintype "input"))
    )
    (net (code "77") (name "unconnected-(FT232RL-OSCO-Pad28)") (class "Default")
      (node (ref "FT232RL") (pin "28") (pinfunction "OSCO_28") (pintype "output"))
    )
    (net (code "78") (name "unconnected-(FT232RL-PWREN-Pad14)") (class "Default")
      (node (ref "FT232RL") (pin "14") (pinfunction "PWREN_14") (pintype "input"))
    )
    (net (code "79") (name "unconnected-(FT232RL-RESET-Pad19)") (class "Default")
      (node (ref "FT232RL") (pin "19") (pinfunction "RESET_19") (pintype "input"))
    )
    (net (code "80") (name "unconnected-(FT232RL-RI-Pad6)") (class "Default")
      (node (ref "FT232RL") (pin "6") (pinfunction "RI_6") (pintype "input"))
    )
    (net (code "81") (name "unconnected-(FT232RL-RTS-Pad3)") (class "Default")
      (node (ref "FT232RL") (pin "3") (pinfunction "RTS_3") (pintype "output"))
    )
    (net (code "82") (name "unconnected-(FT232RL-RXLED-Pad22)") (class "Default")
      (node (ref "FT232RL") (pin "22") (pinfunction "RXLED_22") (pintype "input"))
    )
    (net (code "83") (name "unconnected-(FT232RL-SLEEP-Pad12)") (class "Default")
      (node (ref "FT232RL") (pin "12") (pinfunction "SLEEP_12") (pintype "input"))
    )
    (net (code "84") (name "unconnected-(FT232RL-TXDEN-Pad13)") (class "Default")
      (node (ref "FT232RL") (pin "13") (pinfunction "TXDEN_13") (pintype "input"))
    )
    (net (code "85") (name "unconnected-(FT232RL-TXLED-Pad23)") (class "Default")
      (node (ref "FT232RL") (pin "23") (pinfunction "TXLED_23") (pintype "input"))
    )
    (net (code "86") (name "unconnected-(LTC2950-OFFT-Pad7)") (class "Default")
      (node (ref "LTC2950") (pin "7") (pinfunction "OFFT_7") (pintype "input"))
    )
    (net (code "87") (name "unconnected-(LTC2950-ONT-Pad3)") (class "Default")
      (node (ref "LTC2950") (pin "3") (pinfunction "ONT_3") (pintype "input"))
    )
    (net (code "88") (name "unconnected-(MCP23017-INTA-Pad20)") (class "Default")
      (node (ref "MCP23017") (pin "20") (pinfunction "INTA_20") (pintype "output"))
    )
  )
)
